# carte_bouton.net
KiCad netlist of a schematic drawn in EAGLE
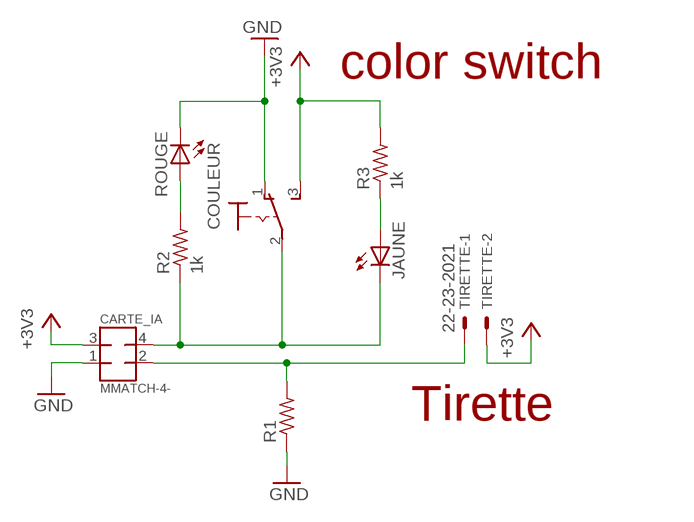
[diagram p0: schematic, sheet 1]

(export (version "E")
  (design (tool "Eeschema 10.0.6"))
  (components
    (comp (ref "CARTE_IA")
      (value "MMATCH-4-")
      (footprint "eagle-import:AMP-215079-4")
      (libsource (lib "eagle-import") (part "MMATCH-4-"))
    )
    (comp (ref "COULEUR")
      (value "320-916")
      (footprint "eagle-import:320-916")
      (libsource (lib "eagle-import") (part "320-916"))
    )
    (comp (ref "JAUNE")
      (value "LEDSML0805")
      (footprint "eagle-import:SML0805")
      (libsource (lib "eagle-import") (part "LEDSML0805"))
    )
    (comp (ref "R1")
      (value "R-US_R0805")
      (footprint "eagle-import:R0805")
      (libsource (lib "eagle-import") (part "R-US_R0805"))
    )
    (comp (ref "R2")
      (value "1k")
      (footprint "eagle-import:M0805")
      (libsource (lib "eagle-import") (part "R-US_M0805"))
    )
    (comp (ref "R3")
      (value "1k")
      (footprint "eagle-import:M0805")
      (libsource (lib "eagle-import") (part "R-US_M0805"))
    )
    (comp (ref "ROUGE")
      (value "LEDSML0805")
      (footprint "eagle-import:SML0805")
      (libsource (lib "eagle-import") (part "LEDSML0805"))
    )
    (comp (ref "TIRETTE")
      (value "22-23-2021")
      (footprint "eagle-import:22-23-2021")
      (fields (field (name "MF") "MOLEX"))
      (libsource (lib "eagle-import") (part "22-23-2021"))
    )
  )
  (nets
    (net (code "1") (name "+3V3") (class "Default")
      (node (ref "CARTE_IA") (pin "3") (pinfunction "7_3") (pintype "bidirectional"))
      (node (ref "COULEUR") (pin "3") (pinfunction "S_3") (pintype "passive"))
      (node (ref "R3") (pin "2") (pinfunction "2_2") (pintype "passive"))
      (node (ref "TIRETTE") (pin "2") (pinfunction "S_2") (pintype "passive"))
    )
    (net (code "2") (name "GND") (class "Default")
      (node (ref "CARTE_IA") (pin "1") (pinfunction "5_1") (pintype "bidirectional"))
      (node (ref "COULEUR") (pin "1") (pinfunction "O_1") (pintype "passive"))
      (node (ref "R1") (pin "1") (pinfunction "1_1") (pintype "passive"))
      (node (ref "ROUGE") (pin "C") (pinfunction "C_C") (pintype "passive"))
    )
    (net (code "3") (name "Net-(CARTE_IA-6)") (class "Default")
      (node (ref "CARTE_IA") (pin "2") (pinfunction "6_2") (pintype "bidirectional"))
      (node (ref "R1") (pin "2") (pinfunction "2_2") (pintype "passive"))
      (node (ref "TIRETTE") (pin "1") (pinfunction "S_1") (pintype "passive"))
    )
    (net (code "4") (name "Net-(CARTE_IA-8)") (class "Default")
      (node (ref "CARTE_IA") (pin "4") (pinfunction "8_4") (pintype "bidirectional"))
      (node (ref "COULEUR") (pin "2") (pinfunction "P_2") (pintype "passive"))
      (node (ref "JAUNE") (pin "C") (pinfunction "C_C") (pintype "passive"))
      (node (ref "R2") (pin "1") (pinfunction "1_1") (pintype "passive"))
    )
    (net (code "5") (name "Net-(JAUNE-PadA)") (class "Default")
      (node (ref "JAUNE") (pin "A") (pinfunction "A_A") (pintype "passive"))
      (node (ref "R3") (pin "1") (pinfunction "1_1") (pintype "passive"))
    )
    (net (code "6") (name "Net-(R2-Pad2)") (class "Default")
      (node (ref "R2") (pin "2") (pinfunction "2_2") (pintype "passive"))
      (node (ref "ROUGE") (pin "A") (pinfunction "A_A") (pintype "passive"))
    )
  )
)
